# ProPrj_AT89C52_LCD12864_2025-10-14.net
KiCad netlist of a schematic drawn in EasyEDA Pro
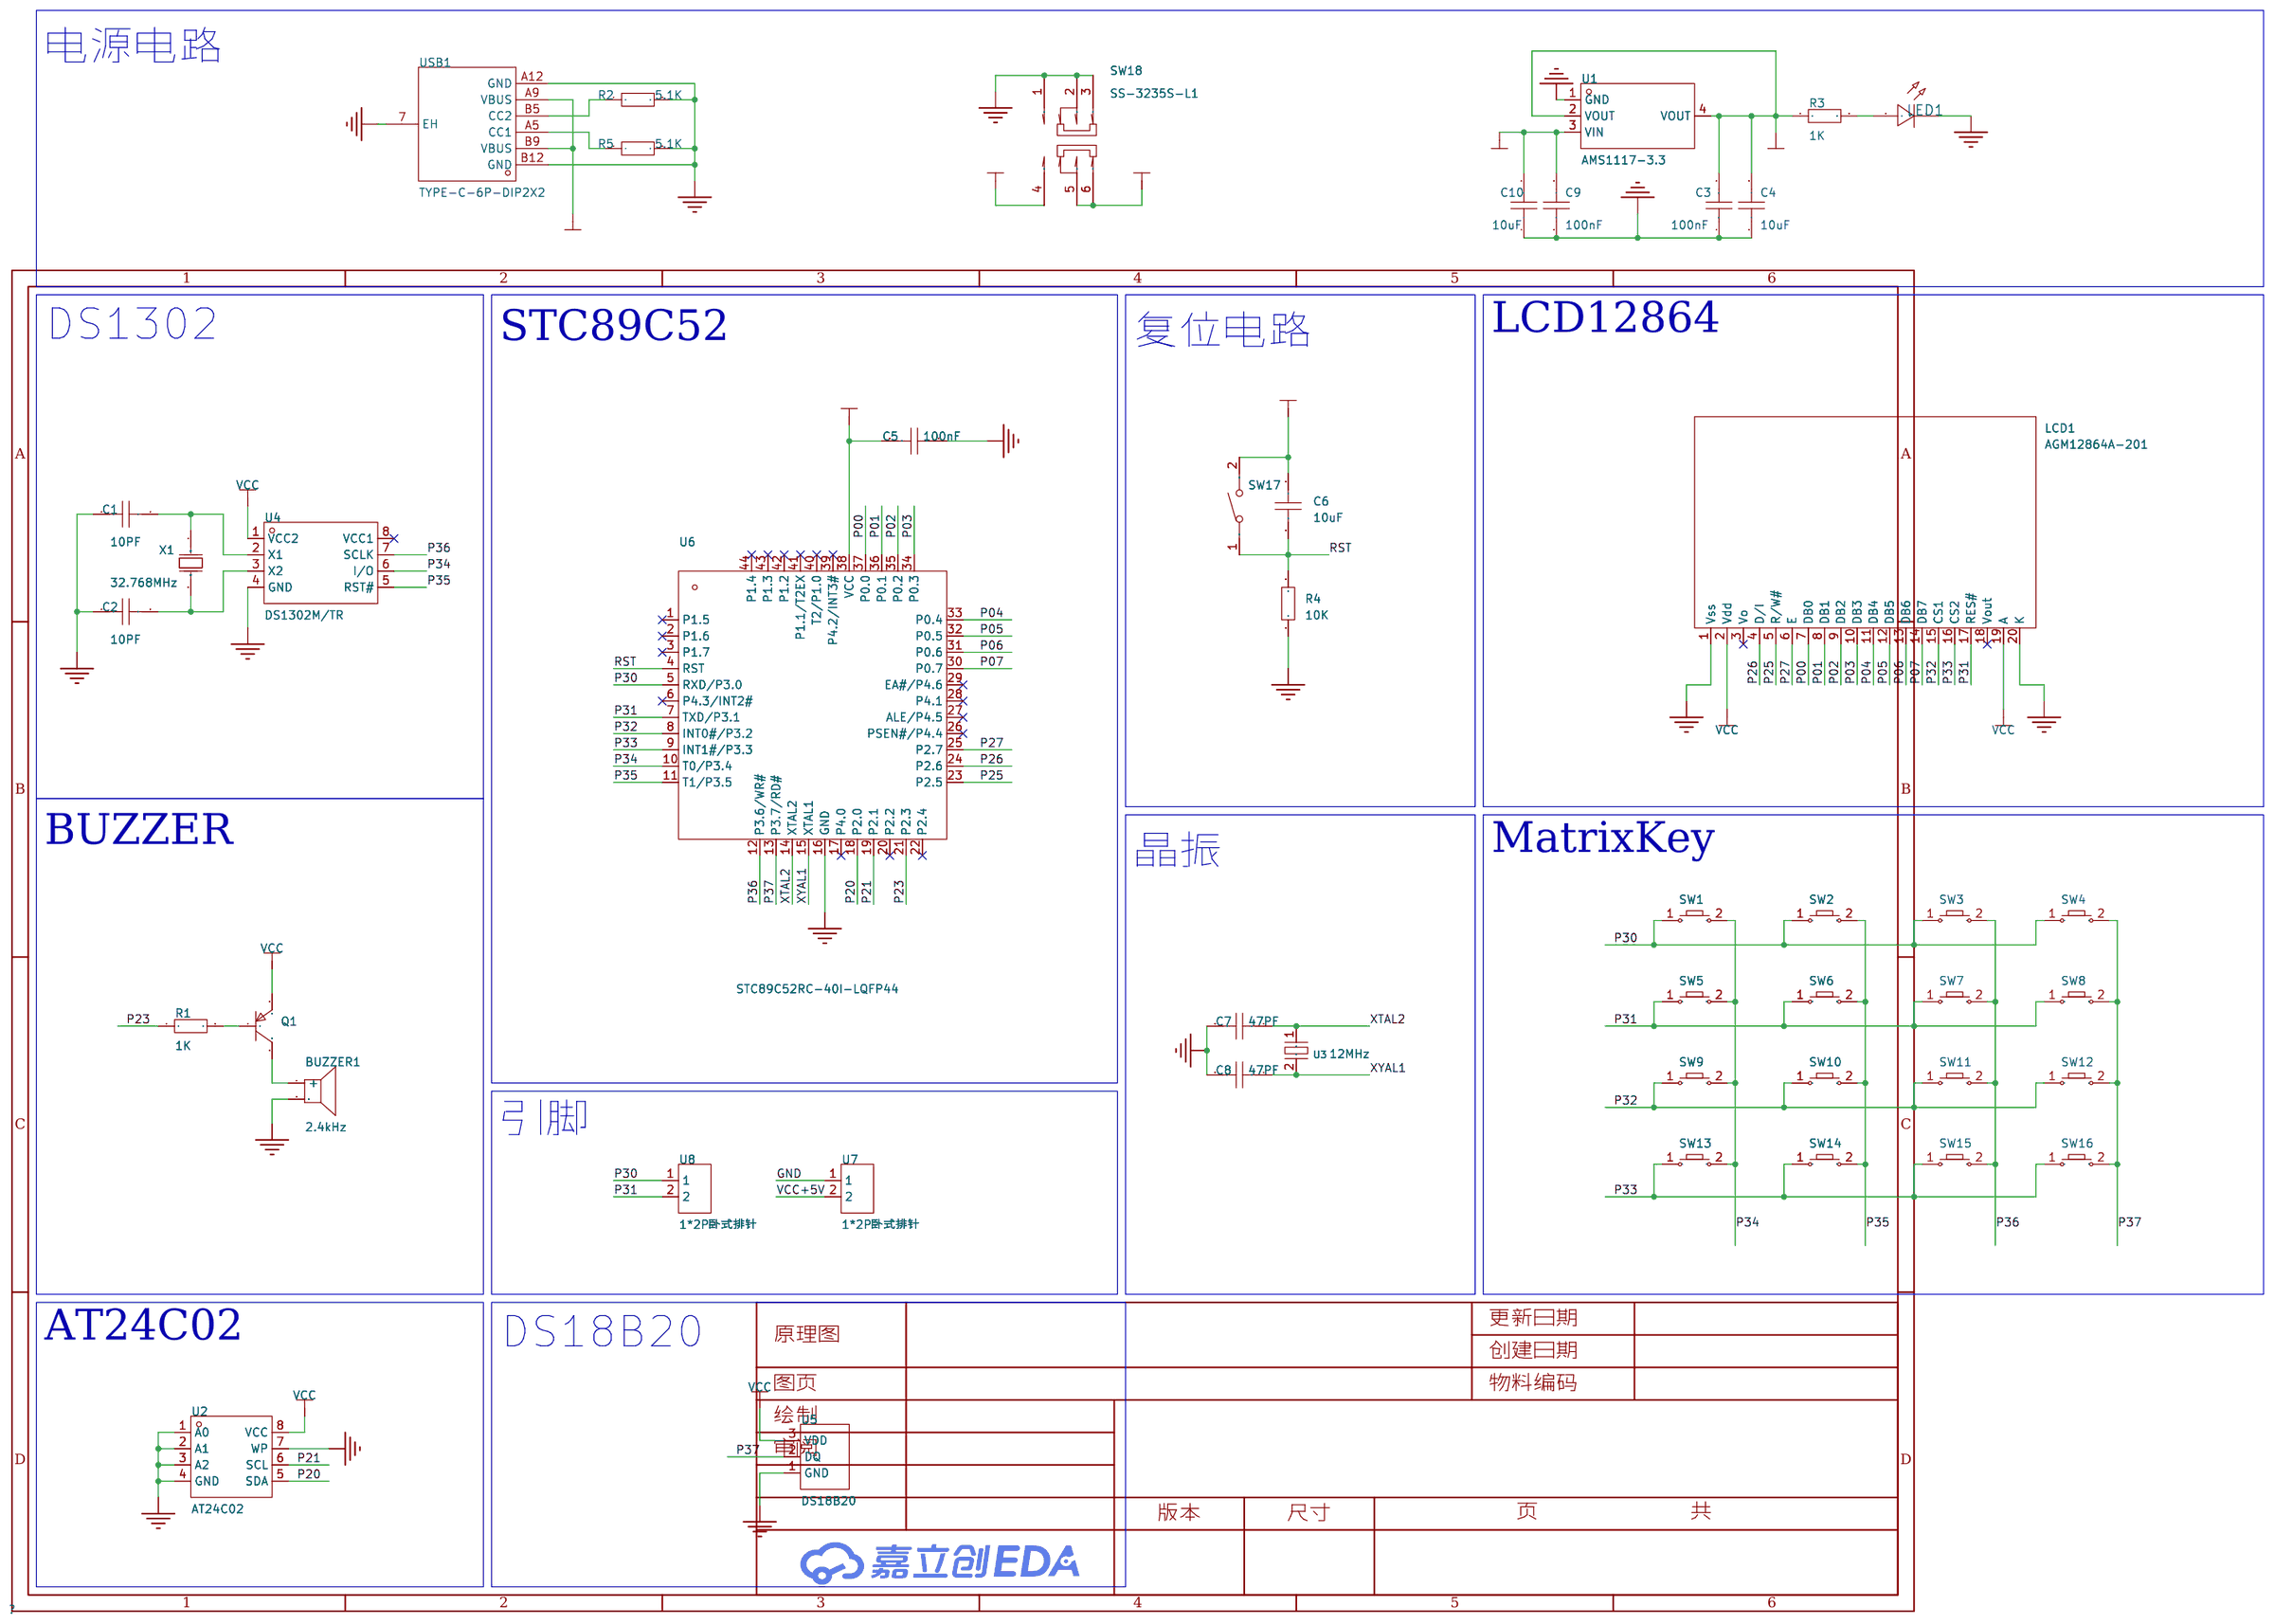
[diagram p0: schematic sheet]

(export (version "E")
  (design (tool "Eeschema 10.0.6"))
  (components
    (comp (ref "BUZZER1")
      (value "2.4kHz")
      (footprint "easyedapro:BUZ-TH_BD12.0-P7.60-D0.6-FD")
      (description "驱动方式:有源(内含驱动线路);构造类型:电磁式;额定电压:-;频率:2.4kHz;声压(SPL):85dB;")
      (fields (field (name "Manufacturer Part") "TMB12A05") (field (name "Manufacturer") "华能"))
      (libsource (lib "easyedapro") (part "TMB12A05"))
    )
    (comp (ref "C1")
      (value "10PF")
      (footprint "easyedapro:C0603")
      (libsource (lib "easyedapro") (part "CapAcitance"))
    )
    (comp (ref "C2")
      (value "10PF")
      (footprint "easyedapro:C0603")
      (libsource (lib "easyedapro") (part "CapAcitance"))
    )
    (comp (ref "C3")
      (value "100nF")
      (footprint "easyedapro:C0603")
      (libsource (lib "easyedapro") (part "CapAcitance"))
    )
    (comp (ref "C4")
      (value "10uF")
      (footprint "easyedapro:C0603")
      (libsource (lib "easyedapro") (part "CapAcitance"))
    )
    (comp (ref "C5")
      (value "100nF")
      (footprint "easyedapro:C0603")
      (libsource (lib "easyedapro") (part "CapAcitance"))
    )
    (comp (ref "C6")
      (value "10uF")
      (footprint "easyedapro:C0603")
      (libsource (lib "easyedapro") (part "CapAcitance"))
    )
    (comp (ref "C7")
      (value "47PF")
      (footprint "easyedapro:C0603")
      (libsource (lib "easyedapro") (part "CapAcitance"))
    )
    (comp (ref "C8")
      (value "47PF")
      (footprint "easyedapro:C0603")
      (libsource (lib "easyedapro") (part "CapAcitance"))
    )
    (comp (ref "C9")
      (value "100nF")
      (footprint "easyedapro:C0603")
      (libsource (lib "easyedapro") (part "CapAcitance"))
    )
    (comp (ref "C10")
      (value "10uF")
      (footprint "easyedapro:C0603")
      (libsource (lib "easyedapro") (part "CapAcitance"))
    )
    (comp (ref "LCD1")
      (value "AGM12864A-201")
      (footprint "easyedapro:LCD-TH_20P-L93.0-W70.0-P2.54_AGM12864A-201")
      (libsource (lib "easyedapro") (part "AGM12864A-201"))
    )
    (comp (ref "LED1")
      (value "~")
      (footprint "easyedapro:LED_0805")
      (libsource (lib "easyedapro") (part "LED_R"))
    )
    (comp (ref "Q1")
      (value "S8550(RANGE:120-200)")
      (footprint "easyedapro:SOT-23-3_L2.9-W1.6-P1.90-LS2.8-BR")
      (description "晶体管类型:PNP;集电极电流(Ic):500mA;集射极击穿电压(Vceo):25V;功率(Pd):300mW;直流电流增益(hFE@Ic,Vce):120@50mA,1V;")
      (fields (field (name "Manufacturer") "CJ(江苏长电/长晶)"))
      (libsource (lib "easyedapro") (part "S8550_C105432"))
    )
    (comp (ref "R1") (value "1K") (footprint "easyedapro:R0603") (libsource (lib "easyedapro") (part "电阻")))
    (comp (ref "R2") (value "5.1K") (footprint "easyedapro:R0805") (libsource (lib "easyedapro") (part "电阻")))
    (comp (ref "R3") (value "1K") (footprint "easyedapro:R0805") (libsource (lib "easyedapro") (part "电阻")))
    (comp (ref "R4") (value "10K") (footprint "easyedapro:R0805") (libsource (lib "easyedapro") (part "电阻")))
    (comp (ref "R5") (value "5.1K") (footprint "easyedapro:R0805") (libsource (lib "easyedapro") (part "电阻")))
    (comp (ref "SW1")
      (value "~")
      (footprint "easyedapro:Key_SMD_3x4x2")
      (libsource (lib "easyedapro") (part "轻触按键x2"))
    )
    (comp (ref "SW2")
      (value "~")
      (footprint "easyedapro:Key_SMD_3x4x2")
      (libsource (lib "easyedapro") (part "轻触按键x2"))
    )
    (comp (ref "SW3")
      (value "~")
      (footprint "easyedapro:Key_SMD_3x4x2")
      (libsource (lib "easyedapro") (part "轻触按键x2"))
    )
    (comp (ref "SW4")
      (value "~")
      (footprint "easyedapro:Key_SMD_3x4x2")
      (libsource (lib "easyedapro") (part "轻触按键x2"))
    )
    (comp (ref "SW5")
      (value "~")
      (footprint "easyedapro:Key_SMD_3x4x2")
      (libsource (lib "easyedapro") (part "轻触按键x2"))
    )
    (comp (ref "SW6")
      (value "~")
      (footprint "easyedapro:Key_SMD_3x4x2")
      (libsource (lib "easyedapro") (part "轻触按键x2"))
    )
    (comp (ref "SW7")
      (value "~")
      (footprint "easyedapro:Key_SMD_3x4x2")
      (libsource (lib "easyedapro") (part "轻触按键x2"))
    )
    (comp (ref "SW8")
      (value "~")
      (footprint "easyedapro:Key_SMD_3x4x2")
      (libsource (lib "easyedapro") (part "轻触按键x2"))
    )
    (comp (ref "SW9")
      (value "~")
      (footprint "easyedapro:Key_SMD_3x4x2")
      (libsource (lib "easyedapro") (part "轻触按键x2"))
    )
    (comp (ref "SW10")
      (value "~")
      (footprint "easyedapro:Key_SMD_3x4x2")
      (libsource (lib "easyedapro") (part "轻触按键x2"))
    )
    (comp (ref "SW11")
      (value "~")
      (footprint "easyedapro:Key_SMD_3x4x2")
      (libsource (lib "easyedapro") (part "轻触按键x2"))
    )
    (comp (ref "SW12")
      (value "~")
      (footprint "easyedapro:Key_SMD_3x4x2")
      (libsource (lib "easyedapro") (part "轻触按键x2"))
    )
    (comp (ref "SW13")
      (value "~")
      (footprint "easyedapro:Key_SMD_3x4x2")
      (libsource (lib "easyedapro") (part "轻触按键x2"))
    )
    (comp (ref "SW14")
      (value "~")
      (footprint "easyedapro:Key_SMD_3x4x2")
      (libsource (lib "easyedapro") (part "轻触按键x2"))
    )
    (comp (ref "SW15")
      (value "~")
      (footprint "easyedapro:Key_SMD_3x4x2")
      (libsource (lib "easyedapro") (part "轻触按键x2"))
    )
    (comp (ref "SW16")
      (value "~")
      (footprint "easyedapro:Key_SMD_3x4x2")
      (libsource (lib "easyedapro") (part "轻触按键x2"))
    )
    (comp (ref "SW17")
      (value "轻触按键3*4*H")
      (footprint "easyedapro:SW-SMD_L4.0-W2.9-LS5.0")
      (libsource (lib "easyedapro") (part "轻触按键3*4*H"))
    )
    (comp (ref "SW18")
      (value "SS-3235S-L1")
      (footprint "easyedapro:SW-SMD_SS-3235S-LX")
      (description "电路结构:双刀双掷;安装方式:卧贴;开关颜色:黑色;额定电流(DC):50mA;额定电压(DC):12V;额定电流(AC):50mA;额定电压(AC):12V;机械寿命:1万次;")
      (fields (field (name "Manufacturer") "XKB Connectivity(中国星坤)"))
      (libsource (lib "easyedapro") (part "SS-3235S-L1"))
    )
    (comp (ref "U1")
      (value "AMS1117-3.3")
      (footprint "easyedapro:SOT-223-3_L6.5-W3.4-P2.30-LS7.0-BR")
      (description "输出类型:固定;最大输入电压:-;输出电压:3.3V;最大输出电流:1A;电源纹波抑制比(PSRR):72dB@(120Hz);输出极性:正极;")
      (fields (field (name "Manufacturer") "AMS"))
      (libsource (lib "easyedapro") (part "AMS1117-3.3"))
    )
    (comp (ref "U2")
      (value "AT24C02")
      (footprint "easyedapro:SOP-8_L5.0-W4.0-P1.27-LS6.0-BL")
      (fields (field (name "Manufacturer") "IDCHIP(英锐芯)"))
      (libsource (lib "easyedapro") (part "AT24C02"))
    )
    (comp (ref "U3")
      (value "12MHz")
      (footprint "easyedapro:CRYSTAL-SMD_L11.4-W4.7-LS12.7")
      (description "频率:12MHz;常温频差:±30ppm;外接负载电容:30pF;频率稳定度(全温):±35ppm;")
      (fields
        (field (name "Manufacturer Part") "ABLS-12.000MHZ-30-A-4-H-T")
        (field (name "Manufacturer") "ABRACON")
      )
      (libsource (lib "easyedapro") (part "ABLS-12.000MHZ-30-A-4-H-T"))
    )
    (comp (ref "U4")
      (value "DS1302M/TR")
      (footprint "easyedapro:SOP-8_L4.9-W3.9-P1.27-LS6.0-BL")
      (fields (field (name "Manufacturer") "HGSEMI(华冠)"))
      (libsource (lib "easyedapro") (part "DS1302M/TR"))
    )
    (comp (ref "U5")
      (value "DS18B20")
      (footprint "easyedapro:TO-92-3_L4.5-W3.5-P1.27-L")
      (description "温度范围:-;精度:±0.4°C;接口类型:-;")
      (fields (field (name "Manufacturer") "HXY MOSFET(华轩阳电子)"))
      (libsource (lib "easyedapro") (part "DS18B20_C5451632"))
    )
    (comp (ref "U6")
      (value "STC89C52RC-40I-LQFP44")
      (footprint "easyedapro:LQFP-44_L10.0-W10.0-P0.80-LS12.0-BL")
      (description "CPU内核:51系列;程序存储容量:8KB;RAM总容量:512Byte;GPIO端口数量:39;工作电压范围:3.3V~5.5V;CPU最大主频:-;程序存储器类型:FLASH;")
      (fields (field (name "Manufacturer") "STC(宏晶)"))
      (libsource (lib "easyedapro") (part "STC89C52RC-40I_C8707"))
    )
    (comp (ref "U7")
      (value "1*2P卧式排针")
      (footprint "easyedapro:HDR-SMD_2P-P2.54-V-M_C9900024210")
      (libsource (lib "easyedapro") (part "1*2P卧式排针"))
    )
    (comp (ref "U8")
      (value "1*2P卧式排针")
      (footprint "easyedapro:HDR-SMD_2P-P2.54-V-M_C9900024210")
      (libsource (lib "easyedapro") (part "1*2P卧式排针"))
    )
    (comp (ref "USB1")
      (value "TYPE-C-6P-DIP2X2")
      (footprint "easyedapro:TYPE-C-SMD_TYPE-C-6P")
      (libsource (lib "easyedapro") (part "TYPE-C-6P-DIP2X2"))
    )
    (comp (ref "X1")
      (value "32.768MHz")
      (footprint "easyedapro:CRYSTAL-SMD_L11.5-W4.8-LS12.7")
      (description "晶振类型:贴片晶振;频率:8MHz;常温频差:±20ppm;负载电容:20pF;频率稳定度:±30ppm;")
      (fields (field (name "Manufacturer Part") "X49SM8MSD2SC") (field (name "Manufacturer") "YXC(扬兴晶振)"))
      (libsource (lib "easyedapro") (part "X49SM8MSD2SC"))
    )
  )
  (nets
    (net (code "1") (name "/P00") (class "Default")
      (node (ref "LCD1") (pin "7") (pinfunction "DB0_7") (pintype "unspecified"))
      (node (ref "U6") (pin "37") (pinfunction "P0.0_37") (pintype "unspecified"))
    )
    (net (code "2") (name "/P01") (class "Default")
      (node (ref "LCD1") (pin "8") (pinfunction "DB1_8") (pintype "unspecified"))
      (node (ref "U6") (pin "36") (pinfunction "P0.1_36") (pintype "unspecified"))
    )
    (net (code "3") (name "/P02") (class "Default")
      (node (ref "LCD1") (pin "9") (pinfunction "DB2_9") (pintype "unspecified"))
      (node (ref "U6") (pin "35") (pinfunction "P0.2_35") (pintype "unspecified"))
    )
    (net (code "4") (name "/P03") (class "Default")
      (node (ref "LCD1") (pin "10") (pinfunction "DB3_10") (pintype "unspecified"))
      (node (ref "U6") (pin "34") (pinfunction "P0.3_34") (pintype "unspecified"))
    )
    (net (code "5") (name "/P04") (class "Default")
      (node (ref "LCD1") (pin "11") (pinfunction "DB4_11") (pintype "unspecified"))
      (node (ref "U6") (pin "33") (pinfunction "P0.4_33") (pintype "unspecified"))
    )
    (net (code "6") (name "/P05") (class "Default")
      (node (ref "LCD1") (pin "12") (pinfunction "DB5_12") (pintype "unspecified"))
      (node (ref "U6") (pin "32") (pinfunction "P0.5_32") (pintype "unspecified"))
    )
    (net (code "7") (name "/P06") (class "Default")
      (node (ref "LCD1") (pin "13") (pinfunction "DB6_13") (pintype "unspecified"))
      (node (ref "U6") (pin "31") (pinfunction "P0.6_31") (pintype "unspecified"))
    )
    (net (code "8") (name "/P07") (class "Default")
      (node (ref "LCD1") (pin "14") (pinfunction "DB7_14") (pintype "unspecified"))
      (node (ref "U6") (pin "30") (pinfunction "P0.7_30") (pintype "unspecified"))
    )
    (net (code "9") (name "/P20") (class "Default")
      (node (ref "U2") (pin "5") (pinfunction "SDA_5") (pintype "unspecified"))
      (node (ref "U6") (pin "18") (pinfunction "P2.0_18") (pintype "unspecified"))
    )
    (net (code "10") (name "/P21") (class "Default")
      (node (ref "U2") (pin "6") (pinfunction "SCL_6") (pintype "unspecified"))
      (node (ref "U6") (pin "19") (pinfunction "P2.1_19") (pintype "unspecified"))
    )
    (net (code "11") (name "/P23") (class "Default")
      (node (ref "R1") (pin "1") (pinfunction "1_1") (pintype "input"))
      (node (ref "U6") (pin "21") (pinfunction "P2.3_21") (pintype "unspecified"))
    )
    (net (code "12") (name "/P25") (class "Default")
      (node (ref "LCD1") (pin "5") (pinfunction "R/W#_5") (pintype "unspecified"))
      (node (ref "U6") (pin "23") (pinfunction "P2.5_23") (pintype "unspecified"))
    )
    (net (code "13") (name "/P26") (class "Default")
      (node (ref "LCD1") (pin "4") (pinfunction "D/I_4") (pintype "unspecified"))
      (node (ref "U6") (pin "24") (pinfunction "P2.6_24") (pintype "unspecified"))
    )
    (net (code "14") (name "/P27") (class "Default")
      (node (ref "LCD1") (pin "6") (pinfunction "E_6") (pintype "unspecified"))
      (node (ref "U6") (pin "25") (pinfunction "P2.7_25") (pintype "unspecified"))
    )
    (net (code "15") (name "/P30") (class "Default")
      (node (ref "SW1") (pin "1") (pinfunction "1_1") (pintype "input"))
      (node (ref "SW2") (pin "1") (pinfunction "1_1") (pintype "input"))
      (node (ref "SW3") (pin "1") (pinfunction "1_1") (pintype "input"))
      (node (ref "SW4") (pin "1") (pinfunction "1_1") (pintype "input"))
      (node (ref "U6") (pin "5") (pinfunction "RXD/P3.0_5") (pintype "unspecified"))
      (node (ref "U8") (pin "1") (pinfunction "1_1") (pintype "unspecified"))
    )
    (net (code "16") (name "/P31") (class "Default")
      (node (ref "LCD1") (pin "17") (pinfunction "RES#_17") (pintype "unspecified"))
      (node (ref "SW5") (pin "1") (pinfunction "1_1") (pintype "input"))
      (node (ref "SW6") (pin "1") (pinfunction "1_1") (pintype "input"))
      (node (ref "SW7") (pin "1") (pinfunction "1_1") (pintype "input"))
      (node (ref "SW8") (pin "1") (pinfunction "1_1") (pintype "input"))
      (node (ref "U6") (pin "7") (pinfunction "TXD/P3.1_7") (pintype "unspecified"))
      (node (ref "U8") (pin "2") (pinfunction "2_2") (pintype "unspecified"))
    )
    (net (code "17") (name "/P32") (class "Default")
      (node (ref "LCD1") (pin "15") (pinfunction "CS1_15") (pintype "unspecified"))
      (node (ref "SW10") (pin "1") (pinfunction "1_1") (pintype "input"))
      (node (ref "SW11") (pin "1") (pinfunction "1_1") (pintype "input"))
      (node (ref "SW12") (pin "1") (pinfunction "1_1") (pintype "input"))
      (node (ref "SW9") (pin "1") (pinfunction "1_1") (pintype "input"))
      (node (ref "U6") (pin "8") (pinfunction "INT0#/P3.2_8") (pintype "unspecified"))
    )
    (net (code "18") (name "/P33") (class "Default")
      (node (ref "LCD1") (pin "16") (pinfunction "CS2_16") (pintype "unspecified"))
      (node (ref "SW13") (pin "1") (pinfunction "1_1") (pintype "input"))
      (node (ref "SW14") (pin "1") (pinfunction "1_1") (pintype "input"))
      (node (ref "SW15") (pin "1") (pinfunction "1_1") (pintype "input"))
      (node (ref "SW16") (pin "1") (pinfunction "1_1") (pintype "input"))
      (node (ref "U6") (pin "9") (pinfunction "INT1#/P3.3_9") (pintype "unspecified"))
    )
    (net (code "19") (name "/P34") (class "Default")
      (node (ref "SW1") (pin "2") (pinfunction "2_2") (pintype "input"))
      (node (ref "SW13") (pin "2") (pinfunction "2_2") (pintype "input"))
      (node (ref "SW5") (pin "2") (pinfunction "2_2") (pintype "input"))
      (node (ref "SW9") (pin "2") (pinfunction "2_2") (pintype "input"))
      (node (ref "U4") (pin "6") (pinfunction "I/O_6") (pintype "unspecified"))
      (node (ref "U6") (pin "10") (pinfunction "T0/P3.4_10") (pintype "unspecified"))
    )
    (net (code "20") (name "/P35") (class "Default")
      (node (ref "SW10") (pin "2") (pinfunction "2_2") (pintype "input"))
      (node (ref "SW14") (pin "2") (pinfunction "2_2") (pintype "input"))
      (node (ref "SW2") (pin "2") (pinfunction "2_2") (pintype "input"))
      (node (ref "SW6") (pin "2") (pinfunction "2_2") (pintype "input"))
      (node (ref "U4") (pin "5") (pinfunction "RST#_5") (pintype "unspecified"))
      (node (ref "U6") (pin "11") (pinfunction "T1/P3.5_11") (pintype "unspecified"))
    )
    (net (code "21") (name "/P36") (class "Default")
      (node (ref "SW11") (pin "2") (pinfunction "2_2") (pintype "input"))
      (node (ref "SW15") (pin "2") (pinfunction "2_2") (pintype "input"))
      (node (ref "SW3") (pin "2") (pinfunction "2_2") (pintype "input"))
      (node (ref "SW7") (pin "2") (pinfunction "2_2") (pintype "input"))
      (node (ref "U4") (pin "7") (pinfunction "SCLK_7") (pintype "unspecified"))
      (node (ref "U6") (pin "12") (pinfunction "P3.6/WR#_12") (pintype "unspecified"))
    )
    (net (code "22") (name "/P37") (class "Default")
      (node (ref "SW12") (pin "2") (pinfunction "2_2") (pintype "input"))
      (node (ref "SW16") (pin "2") (pinfunction "2_2") (pintype "input"))
      (node (ref "SW4") (pin "2") (pinfunction "2_2") (pintype "input"))
      (node (ref "SW8") (pin "2") (pinfunction "2_2") (pintype "input"))
      (node (ref "U5") (pin "2") (pinfunction "DQ_2") (pintype "unspecified"))
      (node (ref "U6") (pin "13") (pinfunction "P3.7/RD#_13") (pintype "unspecified"))
    )
    (net (code "23") (name "/RST") (class "Default")
      (node (ref "C6") (pin "2") (pinfunction "2_2") (pintype "input"))
      (node (ref "R4") (pin "2") (pinfunction "2_2") (pintype "input"))
      (node (ref "SW17") (pin "1") (pinfunction "1_1") (pintype "unspecified"))
      (node (ref "U6") (pin "4") (pinfunction "RST_4") (pintype "unspecified"))
    )
    (net (code "24") (name "/XTAL2") (class "Default")
      (node (ref "C7") (pin "1") (pinfunction "1_1") (pintype "input"))
      (node (ref "U3") (pin "1") (pinfunction "1_1") (pintype "input"))
      (node (ref "U6") (pin "14") (pinfunction "XTAL2_14") (pintype "unspecified"))
    )
    (net (code "25") (name "/XYAL1") (class "Default")
      (node (ref "C8") (pin "1") (pinfunction "1_1") (pintype "input"))
      (node (ref "U3") (pin "2") (pinfunction "GND_2") (pintype "input"))
      (node (ref "U6") (pin "15") (pinfunction "XTAL1_15") (pintype "unspecified"))
    )
    (net (code "26") (name "3.3V") (class "Default")
      (node (ref "C3") (pin "2") (pinfunction "2_2") (pintype "input"))
      (node (ref "C4") (pin "2") (pinfunction "2_2") (pintype "input"))
      (node (ref "R3") (pin "1") (pinfunction "1_1") (pintype "input"))
      (node (ref "U1") (pin "2") (pinfunction "VOUT_2") (pintype "unspecified"))
      (node (ref "U1") (pin "4") (pinfunction "VOUT_4") (pintype "unspecified"))
    )
    (net (code "27") (name "GND") (class "Default")
      (node (ref "BUZZER1") (pin "2") (pinfunction "2_2") (pintype "unspecified"))
      (node (ref "C1") (pin "1") (pinfunction "1_1") (pintype "input"))
      (node (ref "C10") (pin "1") (pinfunction "1_1") (pintype "input"))
      (node (ref "C2") (pin "1") (pinfunction "1_1") (pintype "input"))
      (node (ref "C3") (pin "1") (pinfunction "1_1") (pintype "input"))
      (node (ref "C4") (pin "1") (pinfunction "1_1") (pintype "input"))
      (node (ref "C5") (pin "1") (pinfunction "1_1") (pintype "input"))
      (node (ref "C7") (pin "2") (pinfunction "2_2") (pintype "input"))
      (node (ref "C8") (pin "2") (pinfunction "2_2") (pintype "input"))
      (node (ref "C9") (pin "1") (pinfunction "1_1") (pintype "input"))
      (node (ref "LCD1") (pin "1") (pinfunction "Vss_1") (pintype "unspecified"))
      (node (ref "LCD1") (pin "20") (pinfunction "K_20") (pintype "unspecified"))
      (node (ref "LED1") (pin "1") (pinfunction "C_1") (pintype "input"))
      (node (ref "R2") (pin "2") (pinfunction "2_2") (pintype "input"))
      (node (ref "R4") (pin "1") (pinfunction "1_1") (pintype "input"))
      (node (ref "R5") (pin "2") (pinfunction "2_2") (pintype "input"))
      (node (ref "SW18") (pin "1") (pinfunction "1_1") (pintype "unspecified"))
      (node (ref "SW18") (pin "2") (pinfunction "2_2") (pintype "unspecified"))
      (node (ref "SW18") (pin "3") (pinfunction "3_3") (pintype "unspecified"))
      (node (ref "U1") (pin "1") (pinfunction "GND_1") (pintype "unspecified"))
      (node (ref "U2") (pin "1") (pinfunction "A0_1") (pintype "unspecified"))
      (node (ref "U2") (pin "2") (pinfunction "A1_2") (pintype "unspecified"))
      (node (ref "U2") (pin "3") (pinfunction "A2_3") (pintype "unspecified"))
      (node (ref "U2") (pin "4") (pinfunction "GND_4") (pintype "unspecified"))
      (node (ref "U2") (pin "7") (pinfunction "WP_7") (pintype "unspecified"))
      (node (ref "U4") (pin "4") (pinfunction "GND_4") (pintype "unspecified"))
      (node (ref "U5") (pin "1") (pinfunction "GND_1") (pintype "unspecified"))
      (node (ref "U6") (pin "16") (pinfunction "GND_16") (pintype "unspecified"))
      (node (ref "U7") (pin "1") (pinfunction "1_1") (pintype "unspecified"))
      (node (ref "USB1") (pin "7") (pinfunction "EH_7") (pintype "unspecified"))
      (node (ref "USB1") (pin "A12") (pinfunction "GND_A12") (pintype "unspecified"))
      (node (ref "USB1") (pin "B12") (pinfunction "GND_B12") (pintype "unspecified"))
    )
    (net (code "28") (name "Net-(BUZZER1-+)") (class "Default")
      (node (ref "BUZZER1") (pin "1") (pinfunction "+_1") (pintype "unspecified"))
      (node (ref "Q1") (pin "3") (pinfunction "3_3") (pintype "input"))
    )
    (net (code "29") (name "Net-(LED1-A)") (class "Default")
      (node (ref "LED1") (pin "2") (pinfunction "A_2") (pintype "input"))
      (node (ref "R3") (pin "2") (pinfunction "2_2") (pintype "input"))
    )
    (net (code "30") (name "Net-(Q1-Pad1)") (class "Default")
      (node (ref "Q1") (pin "1") (pinfunction "1_1") (pintype "input"))
      (node (ref "R1") (pin "2") (pinfunction "2_2") (pintype "input"))
    )
    (net (code "31") (name "Net-(U4-X1)") (class "Default")
      (node (ref "C1") (pin "2") (pinfunction "2_2") (pintype "input"))
      (node (ref "U4") (pin "2") (pinfunction "X1_2") (pintype "unspecified"))
      (node (ref "X1") (pin "1") (pinfunction "OSC1_1") (pintype "input"))
    )
    (net (code "32") (name "Net-(U4-X2)") (class "Default")
      (node (ref "C2") (pin "2") (pinfunction "2_2") (pintype "input"))
      (node (ref "U4") (pin "3") (pinfunction "X2_3") (pintype "unspecified"))
      (node (ref "X1") (pin "2") (pinfunction "OSC2_2") (pintype "input"))
    )
    (net (code "33") (name "Net-(USB1-CC1)") (class "Default")
      (node (ref "R5") (pin "1") (pinfunction "1_1") (pintype "input"))
      (node (ref "USB1") (pin "A5") (pinfunction "CC1_A5") (pintype "unspecified"))
    )
    (net (code "34") (name "Net-(USB1-CC2)") (class "Default")
      (node (ref "R2") (pin "1") (pinfunction "1_1") (pintype "input"))
      (node (ref "USB1") (pin "B5") (pinfunction "CC2_B5") (pintype "unspecified"))
    )
    (net (code "35") (name "VCC") (class "Default")
      (node (ref "C10") (pin "2") (pinfunction "2_2") (pintype "input"))
      (node (ref "C5") (pin "2") (pinfunction "2_2") (pintype "input"))
      (node (ref "C6") (pin "1") (pinfunction "1_1") (pintype "input"))
      (node (ref "C9") (pin "2") (pinfunction "2_2") (pintype "input"))
      (node (ref "LCD1") (pin "19") (pinfunction "A_19") (pintype "unspecified"))
      (node (ref "LCD1") (pin "2") (pinfunction "Vdd_2") (pintype "unspecified"))
      (node (ref "Q1") (pin "2") (pinfunction "2_2") (pintype "input"))
      (node (ref "SW17") (pin "2") (pinfunction "2_2") (pintype "unspecified"))
      (node (ref "SW18") (pin "5") (pinfunction "5_5") (pintype "unspecified"))
      (node (ref "SW18") (pin "6") (pinfunction "6_6") (pintype "unspecified"))
      (node (ref "U1") (pin "3") (pinfunction "VIN_3") (pintype "unspecified"))
      (node (ref "U2") (pin "8") (pinfunction "VCC_8") (pintype "unspecified"))
      (node (ref "U4") (pin "1") (pinfunction "VCC2_1") (pintype "unspecified"))
      (node (ref "U5") (pin "3") (pinfunction "VDD_3") (pintype "unspecified"))
      (node (ref "U6") (pin "38") (pinfunction "VCC_38") (pintype "unspecified"))
    )
    (net (code "36") (name "VCC+5V") (class "Default")
      (node (ref "SW18") (pin "4") (pinfunction "4_4") (pintype "unspecified"))
      (node (ref "U7") (pin "2") (pinfunction "2_2") (pintype "unspecified"))
      (node (ref "USB1") (pin "A9") (pinfunction "VBUS_A9") (pintype "unspecified"))
      (node (ref "USB1") (pin "B9") (pinfunction "VBUS_B9") (pintype "unspecified"))
    )
    (net (code "37") (name "unconnected-(LCD1-Vo-Pad3)") (class "Default")
      (node (ref "LCD1") (pin "3") (pinfunction "Vo_3") (pintype "unspecified+no_connect"))
    )
    (net (code "38") (name "unconnected-(LCD1-Vout-Pad18)") (class "Default")
      (node (ref "LCD1") (pin "18") (pinfunction "Vout_18") (pintype "unspecified+no_connect"))
    )
    (net (code "39") (name "unconnected-(U4-VCC1-Pad8)") (class "Default")
      (node (ref "U4") (pin "8") (pinfunction "VCC1_8") (pintype "unspecified+no_connect"))
    )
    (net (code "40") (name "unconnected-(U6-ALE{slash}P4.5-Pad27)") (class "Default")
      (node (ref "U6") (pin "27") (pinfunction "ALE/P4.5_27") (pintype "unspecified+no_connect"))
    )
    (net (code "41") (name "unconnected-(U6-EA#{slash}P4.6-Pad29)") (class "Default")
      (node (ref "U6") (pin "29") (pinfunction "EA#/P4.6_29") (pintype "unspecified+no_connect"))
    )
    (net (code "42") (name "unconnected-(U6-P1.1{slash}T2EX-Pad41)") (class "Default")
      (node (ref "U6") (pin "41") (pinfunction "P1.1/T2EX_41") (pintype "unspecified+no_connect"))
    )
    (net (code "43") (name "unconnected-(U6-P1.2-Pad42)") (class "Default")
      (node (ref "U6") (pin "42") (pinfunction "P1.2_42") (pintype "unspecified+no_connect"))
    )
    (net (code "44") (name "unconnected-(U6-P1.3-Pad43)") (class "Default")
      (node (ref "U6") (pin "43") (pinfunction "P1.3_43") (pintype "unspecified+no_connect"))
    )
    (net (code "45") (name "unconnected-(U6-P1.4-Pad44)") (class "Default")
      (node (ref "U6") (pin "44") (pinfunction "P1.4_44") (pintype "unspecified+no_connect"))
    )
    (net (code "46") (name "unconnected-(U6-P1.5-Pad1)") (class "Default")
      (node (ref "U6") (pin "1") (pinfunction "P1.5_1") (pintype "unspecified+no_connect"))
    )
    (net (code "47") (name "unconnected-(U6-P1.6-Pad2)") (class "Default")
      (node (ref "U6") (pin "2") (pinfunction "P1.6_2") (pintype "unspecified+no_connect"))
    )
    (net (code "48") (name "unconnected-(U6-P1.7-Pad3)") (class "Default")
      (node (ref "U6") (pin "3") (pinfunction "P1.7_3") (pintype "unspecified+no_connect"))
    )
    (net (code "49") (name "unconnected-(U6-P2.2-Pad20)") (class "Default")
      (node (ref "U6") (pin "20") (pinfunction "P2.2_20") (pintype "unspecified+no_connect"))
    )
    (net (code "50") (name "unconnected-(U6-P2.4-Pad22)") (class "Default")
      (node (ref "U6") (pin "22") (pinfunction "P2.4_22") (pintype "unspecified+no_connect"))
    )
    (net (code "51") (name "unconnected-(U6-P4.0-Pad17)") (class "Default")
      (node (ref "U6") (pin "17") (pinfunction "P4.0_17") (pintype "unspecified+no_connect"))
    )
    (net (code "52") (name "unconnected-(U6-P4.1-Pad28)") (class "Default")
      (node (ref "U6") (pin "28") (pinfunction "P4.1_28") (pintype "unspecified+no_connect"))
    )
    (net (code "53") (name "unconnected-(U6-P4.2{slash}INT3#-Pad39)") (class "Default")
      (node (ref "U6") (pin "39") (pinfunction "P4.2/INT3#_39") (pintype "unspecified+no_connect"))
    )
    (net (code "54") (name "unconnected-(U6-P4.3{slash}INT2#-Pad6)") (class "Default")
      (node (ref "U6") (pin "6") (pinfunction "P4.3/INT2#_6") (pintype "unspecified+no_connect"))
    )
    (net (code "55") (name "unconnected-(U6-PSEN#{slash}P4.4-Pad26)") (class "Default")
      (node (ref "U6") (pin "26") (pinfunction "PSEN#/P4.4_26") (pintype "unspecified+no_connect"))
    )
    (net (code "56") (name "unconnected-(U6-T2{slash}P1.0-Pad40)") (class "Default")
      (node (ref "U6") (pin "40") (pinfunction "T2/P1.0_40") (pintype "unspecified+no_connect"))
    )
  )
)
